# p1am-proto-iso-rs485-v1.net
KiCad netlist of a schematic drawn in EAGLE
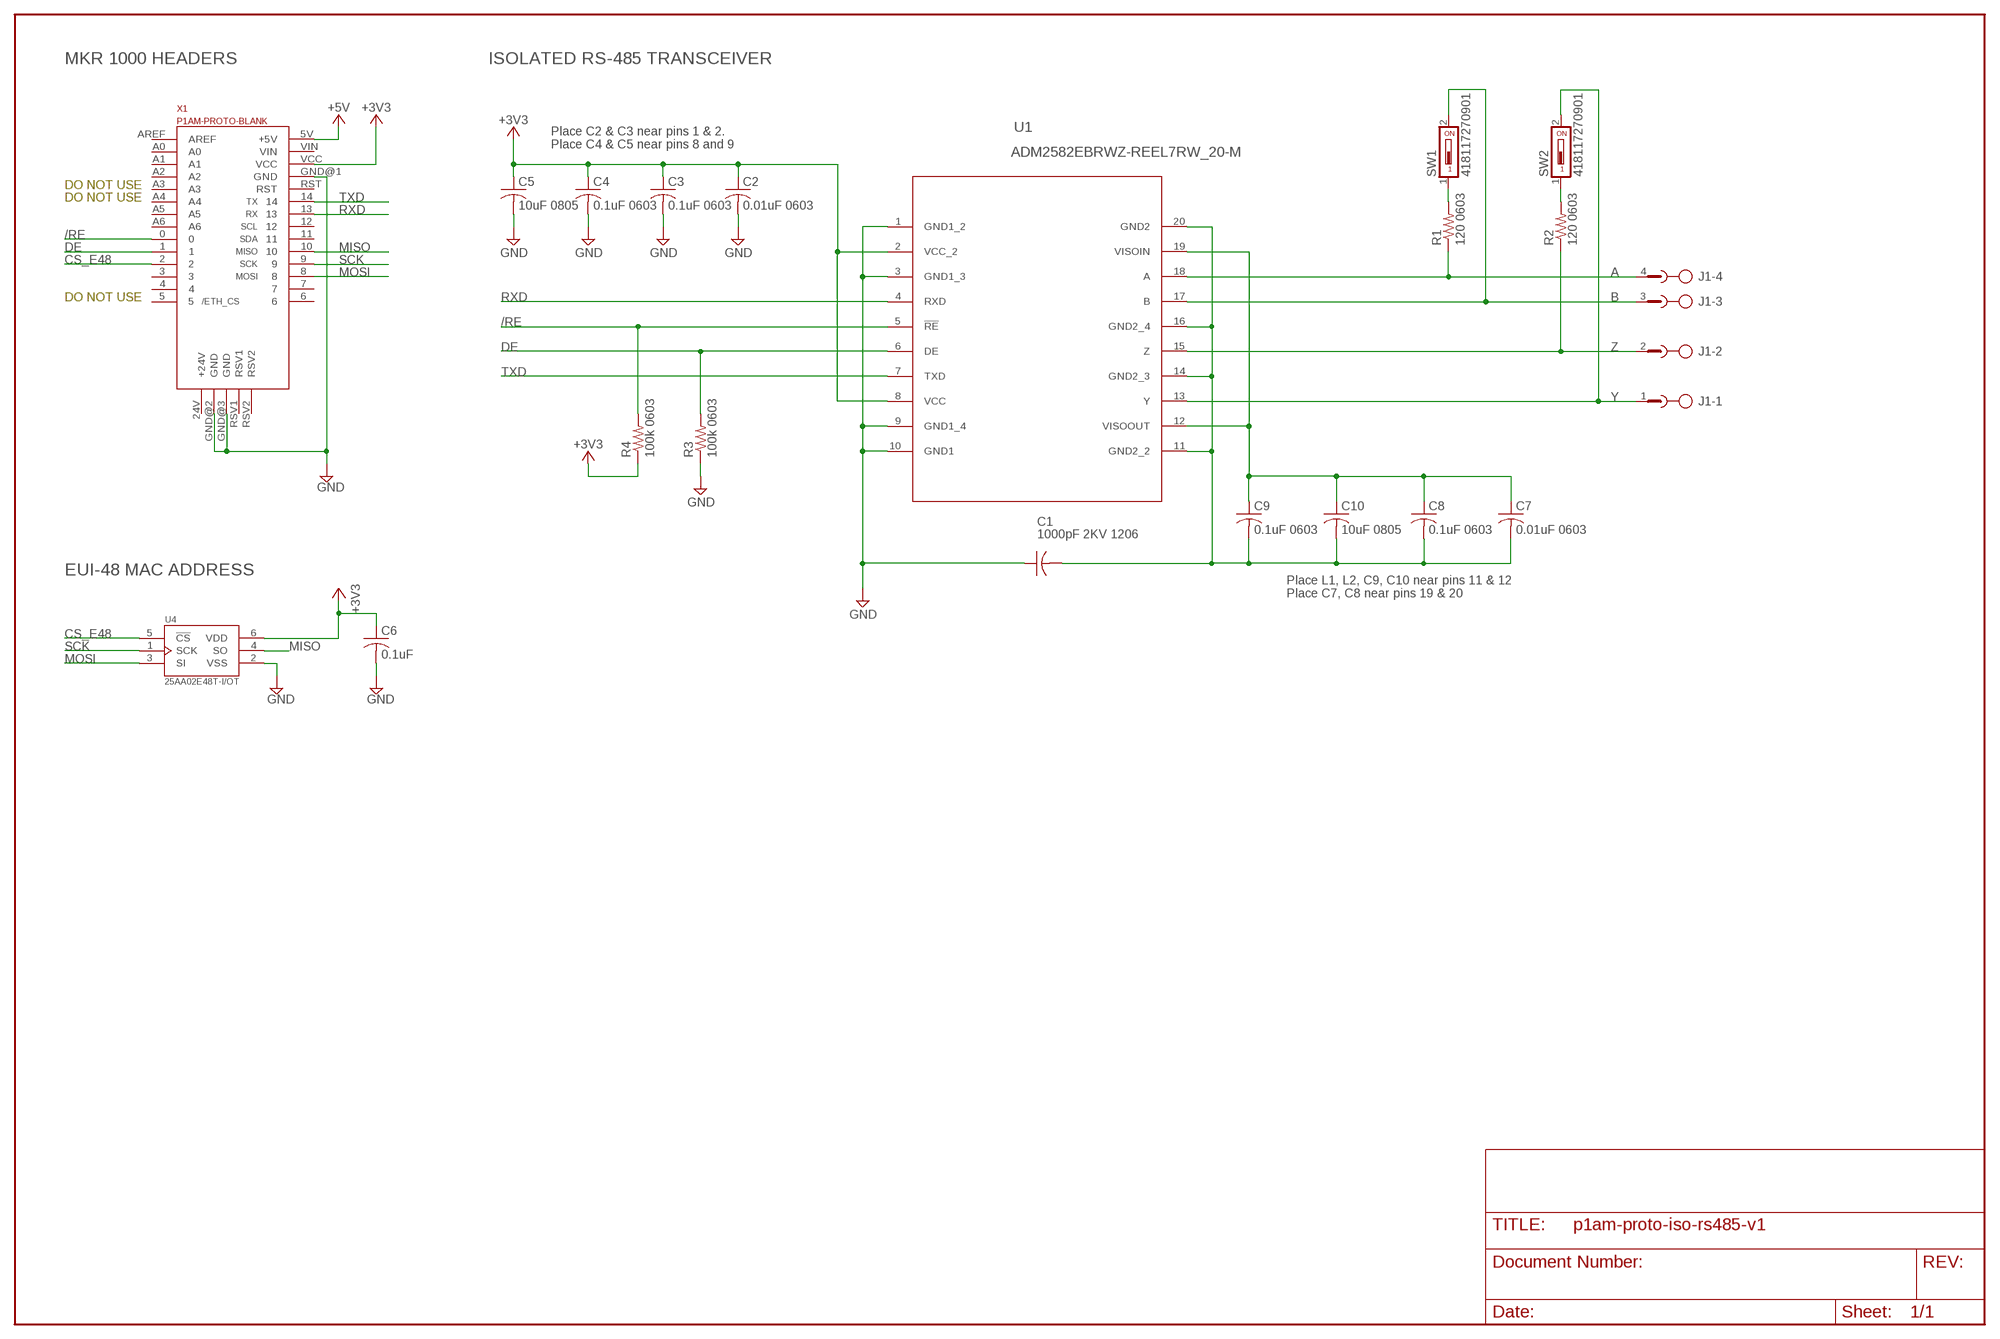
[diagram p0: schematic, sheet 1]

(export (version "E")
  (design (tool "Eeschema 10.0.6"))
  (components
    (comp (ref "C1")
      (value "1000pF 2KV 1206")
      (footprint "eagle-import:C1206K")
      (libsource (lib "eagle-import") (part "C-USC1206K"))
    )
    (comp (ref "C2")
      (value "0.01uF 0603")
      (footprint "eagle-import:C0603K")
      (libsource (lib "eagle-import") (part "C-USC0603K"))
    )
    (comp (ref "C3")
      (value "0.1uF 0603")
      (footprint "eagle-import:C0603K")
      (libsource (lib "eagle-import") (part "C-USC0603K"))
    )
    (comp (ref "C4")
      (value "0.1uF 0603")
      (footprint "eagle-import:C0603K")
      (libsource (lib "eagle-import") (part "C-USC0603K"))
    )
    (comp (ref "C5")
      (value "10uF 0805")
      (footprint "eagle-import:C0805K")
      (libsource (lib "eagle-import") (part "C-USC0805K"))
    )
    (comp (ref "C6")
      (value "0.1uF")
      (footprint "eagle-import:C0603")
      (libsource (lib "eagle-import") (part "C-USC0603"))
    )
    (comp (ref "C7")
      (value "0.01uF 0603")
      (footprint "eagle-import:C0603K")
      (libsource (lib "eagle-import") (part "C-USC0603K"))
    )
    (comp (ref "C8")
      (value "0.1uF 0603")
      (footprint "eagle-import:C0603K")
      (libsource (lib "eagle-import") (part "C-USC0603K"))
    )
    (comp (ref "C9")
      (value "0.1uF 0603")
      (footprint "eagle-import:C0603K")
      (libsource (lib "eagle-import") (part "C-USC0603K"))
    )
    (comp (ref "C10")
      (value "10uF 0805")
      (footprint "eagle-import:C0805K")
      (libsource (lib "eagle-import") (part "C-USC0805K"))
    )
    (comp (ref "J1")
      (value "PHOENIX-XXXXXXX-TERM-BLOCK-HDR-4POS-90DEG-3.5MM")
      (footprint "eagle-import:PHOENIX-XXXXXXX-TERM-BLOCK-HDR-4POS-90DEG-3.5MM")
      (libsource (lib "eagle-import") (part "PHOENIX-XXXXXXX-TERM-BLOCK-HDR-4POS-90DEG-3.5MM"))
    )
    (comp (ref "R1")
      (value "120 0603")
      (footprint "eagle-import:R0603")
      (libsource (lib "eagle-import") (part "R-US_R0603"))
    )
    (comp (ref "R2")
      (value "120 0603")
      (footprint "eagle-import:R0603")
      (libsource (lib "eagle-import") (part "R-US_R0603"))
    )
    (comp (ref "R3")
      (value "100k 0603")
      (footprint "eagle-import:R0603")
      (libsource (lib "eagle-import") (part "R-US_R0603"))
    )
    (comp (ref "R4")
      (value "100k 0603")
      (footprint "eagle-import:R0603")
      (libsource (lib "eagle-import") (part "R-US_R0603"))
    )
    (comp (ref "SW1")
      (value "418117270901")
      (footprint "eagle-import:DIP-01-PTH")
      (libsource (lib "eagle-import") (part "418117270901"))
    )
    (comp (ref "SW2")
      (value "418117270901")
      (footprint "eagle-import:DIP-01-PTH")
      (libsource (lib "eagle-import") (part "418117270901"))
    )
    (comp (ref "U1")
      (value "ADM2582EBRWZ-REEL7RW_20-M")
      (footprint "eagle-import:RW_20-M")
      (fields
        (field (name "MANUFACTURER_PART_NUMBER") "ADM2582EBRWZ-REEL7")
        (field (name "COPYRIGHT") "Copyright (C) 2018 Accelerated Designs. All rights reserved")
      )
      (libsource (lib "eagle-import") (part "ADM2582EBRWZ-REEL7RW_20-M"))
    )
    (comp (ref "U4")
      (value "25AA02E48T-I/OT")
      (footprint "eagle-import:SOT95P270X145-6N")
      (fields (field (name "DIGI-KEY_PART_NUMBER") "25AA02E48T-I/OTCT-ND") (field (name "MF") "Microchip"))
      (libsource (lib "eagle-import") (part "25AA02E48T-I/OT"))
    )
    (comp (ref "X1")
      (value "P1AM-PROTO-BLANK")
      (footprint "eagle-import:P1AM-PROTO-BLANK")
      (libsource (lib "eagle-import") (part "P1AM-PROTO-BLANK"))
    )
  )
  (nets
    (net (code "1") (name "+3V3") (class "Default")
      (node (ref "C2") (pin "1") (pinfunction "1_1") (pintype "passive"))
      (node (ref "C3") (pin "1") (pinfunction "1_1") (pintype "passive"))
      (node (ref "C4") (pin "1") (pinfunction "1_1") (pintype "passive"))
      (node (ref "C5") (pin "1") (pinfunction "1_1") (pintype "passive"))
      (node (ref "C6") (pin "1") (pinfunction "1_1") (pintype "passive"))
      (node (ref "R4") (pin "1") (pinfunction "1_1") (pintype "passive"))
      (node (ref "U1") (pin "2") (pinfunction "VCC_2_2") (pintype "power_in"))
      (node (ref "U1") (pin "8") (pinfunction "VCC_8") (pintype "power_in"))
      (node (ref "U4") (pin "6") (pinfunction "VDD_6") (pintype "power_in"))
      (node (ref "X1") (pin "VCC") (pinfunction "VCC_VCC") (pintype "bidirectional"))
    )
    (net (code "2") (name "+5V") (class "Default")
      (node (ref "X1") (pin "5V") (pinfunction "+5V_5V") (pintype "bidirectional"))
    )
    (net (code "3") (name "/A") (class "Default")
      (node (ref "J1") (pin "4") (pinfunction "1_4") (pintype "passive"))
      (node (ref "R1") (pin "1") (pinfunction "1_1") (pintype "passive"))
      (node (ref "U1") (pin "18") (pinfunction "A_18") (pintype "passive"))
    )
    (net (code "4") (name "/B") (class "Default")
      (node (ref "J1") (pin "3") (pinfunction "1_3") (pintype "passive"))
      (node (ref "SW1") (pin "2") (pinfunction "2_2") (pintype "passive"))
      (node (ref "U1") (pin "17") (pinfunction "B_17") (pintype "passive"))
    )
    (net (code "5") (name "/CS_E48") (class "Default")
      (node (ref "U4") (pin "5") (pinfunction "~{CS}_5") (pintype "input"))
      (node (ref "X1") (pin "2") (pinfunction "2_2") (pintype "bidirectional"))
    )
    (net (code "6") (name "/DE") (class "Default")
      (node (ref "R3") (pin "2") (pinfunction "2_2") (pintype "passive"))
      (node (ref "U1") (pin "6") (pinfunction "DE_6") (pintype "passive"))
      (node (ref "X1") (pin "1") (pinfunction "1_1") (pintype "bidirectional"))
    )
    (net (code "7") (name "/MISO") (class "Default")
      (node (ref "U4") (pin "4") (pinfunction "SO_4") (pintype "output"))
      (node (ref "X1") (pin "10") (pinfunction "10_10") (pintype "bidirectional"))
    )
    (net (code "8") (name "/MOSI") (class "Default")
      (node (ref "U4") (pin "3") (pinfunction "SI_3") (pintype "input"))
      (node (ref "X1") (pin "8") (pinfunction "8_8") (pintype "bidirectional"))
    )
    (net (code "9") (name "/RXD") (class "Default")
      (node (ref "U1") (pin "4") (pinfunction "RXD_4") (pintype "passive"))
      (node (ref "X1") (pin "13") (pinfunction "13_13") (pintype "bidirectional"))
    )
    (net (code "10") (name "/SCK") (class "Default")
      (node (ref "U4") (pin "1") (pinfunction "SCK_1") (pintype "input"))
      (node (ref "X1") (pin "9") (pinfunction "9_9") (pintype "bidirectional"))
    )
    (net (code "11") (name "/TXD") (class "Default")
      (node (ref "U1") (pin "7") (pinfunction "TXD_7") (pintype "passive"))
      (node (ref "X1") (pin "14") (pinfunction "14_14") (pintype "bidirectional"))
    )
    (net (code "12") (name "/Y") (class "Default")
      (node (ref "J1") (pin "1") (pinfunction "1_1") (pintype "passive"))
      (node (ref "SW2") (pin "2") (pinfunction "2_2") (pintype "passive"))
      (node (ref "U1") (pin "13") (pinfunction "Y_13") (pintype "passive"))
    )
    (net (code "13") (name "/Z") (class "Default")
      (node (ref "J1") (pin "2") (pinfunction "1_2") (pintype "passive"))
      (node (ref "R2") (pin "1") (pinfunction "1_1") (pintype "passive"))
      (node (ref "U1") (pin "15") (pinfunction "Z_15") (pintype "passive"))
    )
    (net (code "14") (name "/{slash}RE") (class "Default")
      (node (ref "R4") (pin "2") (pinfunction "2_2") (pintype "passive"))
      (node (ref "U1") (pin "5") (pinfunction "~{RE}_5") (pintype "passive"))
      (node (ref "X1") (pin "0") (pinfunction "0_0") (pintype "bidirectional"))
    )
    (net (code "15") (name "GND") (class "Default")
      (node (ref "C1") (pin "1") (pinfunction "1_1") (pintype "passive"))
      (node (ref "C2") (pin "2") (pinfunction "2_2") (pintype "passive"))
      (node (ref "C3") (pin "2") (pinfunction "2_2") (pintype "passive"))
      (node (ref "C4") (pin "2") (pinfunction "2_2") (pintype "passive"))
      (node (ref "C5") (pin "2") (pinfunction "2_2") (pintype "passive"))
      (node (ref "C6") (pin "2") (pinfunction "2_2") (pintype "passive"))
      (node (ref "R3") (pin "1") (pinfunction "1_1") (pintype "passive"))
      (node (ref "U1") (pin "1") (pinfunction "GND1_2_1") (pintype "passive"))
      (node (ref "U1") (pin "10") (pinfunction "GND1_10") (pintype "passive"))
      (node (ref "U1") (pin "3") (pinfunction "GND1_3_3") (pintype "passive"))
      (node (ref "U1") (pin "9") (pinfunction "GND1_4_9") (pintype "passive"))
      (node (ref "U4") (pin "2") (pinfunction "VSS_2") (pintype "power_in"))
      (node (ref "X1") (pin "GND@1") (pinfunction "GND_GND@1") (pintype "bidirectional"))
      (node (ref "X1") (pin "GND@2") (pinfunction "GND_GND@2") (pintype "bidirectional"))
      (node (ref "X1") (pin "GND@3") (pinfunction "GND_GND@3") (pintype "bidirectional"))
    )
    (net (code "16") (name "Net-(R1-Pad2)") (class "Default")
      (node (ref "R1") (pin "2") (pinfunction "2_2") (pintype "passive"))
      (node (ref "SW1") (pin "1") (pinfunction "1_1") (pintype "passive"))
    )
    (net (code "17") (name "Net-(R2-Pad2)") (class "Default")
      (node (ref "R2") (pin "2") (pinfunction "2_2") (pintype "passive"))
      (node (ref "SW2") (pin "1") (pinfunction "1_1") (pintype "passive"))
    )
    (net (code "18") (name "Net-(U1-GND2)") (class "Default")
      (node (ref "C1") (pin "2") (pinfunction "2_2") (pintype "passive"))
      (node (ref "C10") (pin "2") (pinfunction "2_2") (pintype "passive"))
      (node (ref "C7") (pin "2") (pinfunction "2_2") (pintype "passive"))
      (node (ref "C8") (pin "2") (pinfunction "2_2") (pintype "passive"))
      (node (ref "C9") (pin "2") (pinfunction "2_2") (pintype "passive"))
      (node (ref "U1") (pin "11") (pinfunction "GND2_2_11") (pintype "passive"))
      (node (ref "U1") (pin "14") (pinfunction "GND2_3_14") (pintype "passive"))
      (node (ref "U1") (pin "16") (pinfunction "GND2_4_16") (pintype "passive"))
      (node (ref "U1") (pin "20") (pinfunction "GND2_20") (pintype "passive"))
    )
    (net (code "19") (name "Net-(U1-VISOIN)") (class "Default")
      (node (ref "C10") (pin "1") (pinfunction "1_1") (pintype "passive"))
      (node (ref "C7") (pin "1") (pinfunction "1_1") (pintype "passive"))
      (node (ref "C8") (pin "1") (pinfunction "1_1") (pintype "passive"))
      (node (ref "C9") (pin "1") (pinfunction "1_1") (pintype "passive"))
      (node (ref "U1") (pin "12") (pinfunction "VISOOUT_12") (pintype "output"))
      (node (ref "U1") (pin "19") (pinfunction "VISOIN_19") (pintype "passive"))
    )
    (net (code "20") (name "unconnected-(X1-+24V-Pad24V)") (class "Default")
      (node (ref "X1") (pin "24V") (pinfunction "+24V_24V") (pintype "bidirectional"))
    )
    (net (code "21") (name "unconnected-(X1-Pad3)") (class "Default")
      (node (ref "X1") (pin "3") (pinfunction "3_3") (pintype "bidirectional"))
    )
    (net (code "22") (name "unconnected-(X1-Pad4)") (class "Default")
      (node (ref "X1") (pin "4") (pinfunction "4_4") (pintype "bidirectional"))
    )
    (net (code "23") (name "unconnected-(X1-Pad5)") (class "Default")
      (node (ref "X1") (pin "5") (pinfunction "5_5") (pintype "bidirectional"))
    )
    (net (code "24") (name "unconnected-(X1-Pad6)") (class "Default")
      (node (ref "X1") (pin "6") (pinfunction "6_6") (pintype "bidirectional"))
    )
    (net (code "25") (name "unconnected-(X1-Pad7)") (class "Default")
      (node (ref "X1") (pin "7") (pinfunction "7_7") (pintype "bidirectional"))
    )
    (net (code "26") (name "unconnected-(X1-Pad11)") (class "Default")
      (node (ref "X1") (pin "11") (pinfunction "11_11") (pintype "bidirectional"))
    )
    (net (code "27") (name "unconnected-(X1-Pad12)") (class "Default")
      (node (ref "X1") (pin "12") (pinfunction "12_12") (pintype "bidirectional"))
    )
    (net (code "28") (name "unconnected-(X1-PadA0)") (class "Default")
      (node (ref "X1") (pin "A0") (pinfunction "A0_A0") (pintype "bidirectional"))
    )
    (net (code "29") (name "unconnected-(X1-PadA1)") (class "Default")
      (node (ref "X1") (pin "A1") (pinfunction "A1_A1") (pintype "bidirectional"))
    )
    (net (code "30") (name "unconnected-(X1-PadA2)") (class "Default")
      (node (ref "X1") (pin "A2") (pinfunction "A2_A2") (pintype "bidirectional"))
    )
    (net (code "31") (name "unconnected-(X1-PadA3)") (class "Default")
      (node (ref "X1") (pin "A3") (pinfunction "A3_A3") (pintype "bidirectional"))
    )
    (net (code "32") (name "unconnected-(X1-PadA4)") (class "Default")
      (node (ref "X1") (pin "A4") (pinfunction "A4_A4") (pintype "bidirectional"))
    )
    (net (code "33") (name "unconnected-(X1-PadA5)") (class "Default")
      (node (ref "X1") (pin "A5") (pinfunction "A5_A5") (pintype "bidirectional"))
    )
    (net (code "34") (name "unconnected-(X1-PadA6)") (class "Default")
      (node (ref "X1") (pin "A6") (pinfunction "A6_A6") (pintype "bidirectional"))
    )
    (net (code "35") (name "unconnected-(X1-PadAREF)") (class "Default")
      (node (ref "X1") (pin "AREF") (pinfunction "AREF_AREF") (pintype "bidirectional"))
    )
    (net (code "36") (name "unconnected-(X1-PadRST)") (class "Default")
      (node (ref "X1") (pin "RST") (pinfunction "RST_RST") (pintype "bidirectional"))
    )
    (net (code "37") (name "unconnected-(X1-PadRSV1)") (class "Default")
      (node (ref "X1") (pin "RSV1") (pinfunction "RSV1_RSV1") (pintype "bidirectional"))
    )
    (net (code "38") (name "unconnected-(X1-PadRSV2)") (class "Default")
      (node (ref "X1") (pin "RSV2") (pinfunction "RSV2_RSV2") (pintype "bidirectional"))
    )
    (net (code "39") (name "unconnected-(X1-PadVIN)") (class "Default")
      (node (ref "X1") (pin "VIN") (pinfunction "VIN_VIN") (pintype "bidirectional"))
    )
  )
)
